# ventiladores.net
KiCad netlist of a schematic drawn in EAGLE
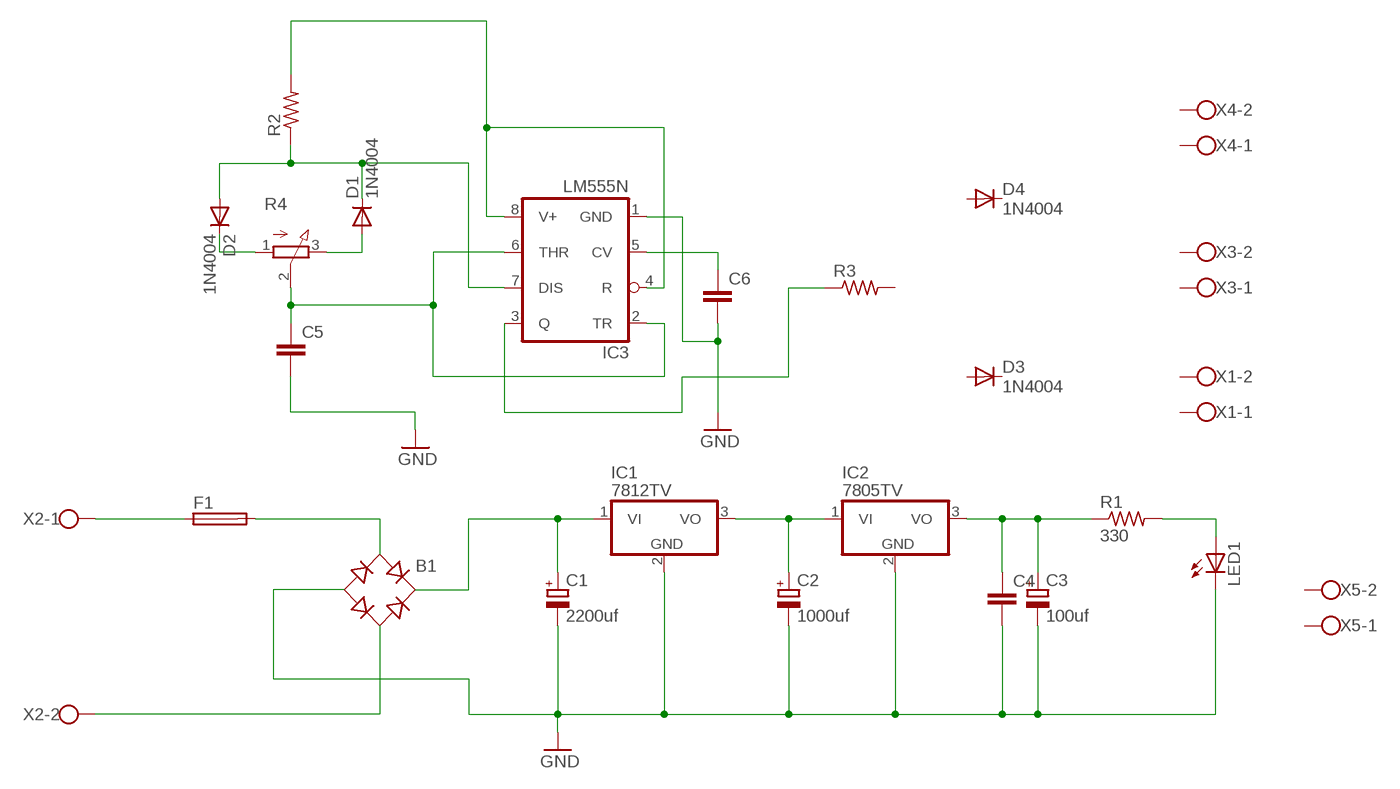
[diagram p0: schematic, sheet 1]

(export (version "E")
  (design (tool "Eeschema 10.0.6"))
  (components
    (comp (ref "B1")
      (value "RB1A")
      (footprint "eagle-import:RB1A")
      (libsource (lib "eagle-import") (part "RB1A"))
    )
    (comp (ref "C1")
      (value "2200uf")
      (footprint "eagle-import:E5-13")
      (libsource (lib "eagle-import") (part "CPOL-EUE5-13"))
    )
    (comp (ref "C2")
      (value "1000uf")
      (footprint "eagle-import:E5-10,5")
      (libsource (lib "eagle-import") (part "CPOL-EUE5-10.5"))
    )
    (comp (ref "C3")
      (value "100uf")
      (footprint "eagle-import:E2,5-6")
      (libsource (lib "eagle-import") (part "CPOL-EUE2.5-6"))
    )
    (comp (ref "C4")
      (value "C2.5/2")
      (footprint "eagle-import:C2.5-2")
      (libsource (lib "eagle-import") (part "C2.5/2"))
    )
    (comp (ref "C5")
      (value "C2.5/2")
      (footprint "eagle-import:C2.5-2")
      (libsource (lib "eagle-import") (part "C2.5/2"))
    )
    (comp (ref "C6")
      (value "C2.5/2")
      (footprint "eagle-import:C2.5-2")
      (libsource (lib "eagle-import") (part "C2.5/2"))
    )
    (comp (ref "D1")
      (value "1N4004")
      (footprint "eagle-import:DO41-10")
      (libsource (lib "eagle-import") (part "1N4004"))
    )
    (comp (ref "D2")
      (value "1N4004")
      (footprint "eagle-import:DO41-10")
      (libsource (lib "eagle-import") (part "1N4004"))
    )
    (comp (ref "D3")
      (value "1N4004")
      (footprint "eagle-import:DO41-10")
      (libsource (lib "eagle-import") (part "1N4004"))
    )
    (comp (ref "D4")
      (value "1N4004")
      (footprint "eagle-import:DO41-10")
      (libsource (lib "eagle-import") (part "1N4004"))
    )
    (comp (ref "F1")
      (value "GSH15")
      (footprint "eagle-import:GSH15")
      (fields (field (name "MPN") "64900001039"))
      (libsource (lib "eagle-import") (part "GSH15"))
    )
    (comp (ref "IC1")
      (value "7812TV")
      (footprint "eagle-import:TO220V")
      (libsource (lib "eagle-import") (part "78TV12"))
    )
    (comp (ref "IC2")
      (value "7805TV")
      (footprint "eagle-import:TO220V")
      (libsource (lib "eagle-import") (part "78TV05"))
    )
    (comp (ref "IC3")
      (value "LM555N")
      (footprint "eagle-import:DIL08")
      (libsource (lib "eagle-import") (part "555NLM"))
    )
    (comp (ref "LED1")
      (value "LED5MM")
      (footprint "eagle-import:LED5MM")
      (libsource (lib "eagle-import") (part "LED5MM"))
    )
    (comp (ref "R1")
      (value "330")
      (footprint "eagle-import:0204_5")
      (libsource (lib "eagle-import") (part "R-US_0204/5"))
    )
    (comp (ref "R2")
      (value "R-US_0207/7")
      (footprint "eagle-import:0207_7")
      (libsource (lib "eagle-import") (part "resistor_R-US_0207/7"))
    )
    (comp (ref "R3")
      (value "R-US_0207/7")
      (footprint "eagle-import:0207_7")
      (libsource (lib "eagle-import") (part "resistor_R-US_0207/7"))
    )
    (comp (ref "R4")
      (value "3RP/1610N")
      (footprint "eagle-import:3RP_1610N")
      (libsource (lib "eagle-import") (part "3RP/1610N"))
    )
    (comp (ref "X1")
      (value "W237-102")
      (footprint "eagle-import:W237-102")
      (fields
        (field (name "MPN") "237-102")
        (field (name "MPN_1") "237-102")
        (field (name "OC_FARNELL") "unknown")
        (field (name "OC_NEWARK") "70K9898")
      )
      (libsource (lib "eagle-import") (part "W237-102"))
    )
    (comp (ref "X2")
      (value "W237-102")
      (footprint "eagle-import:W237-102")
      (fields (field (name "MPN") "237-102"))
      (libsource (lib "eagle-import") (part "W237-102"))
    )
    (comp (ref "X3")
      (value "W237-102")
      (footprint "eagle-import:W237-102")
      (fields
        (field (name "MPN") "237-102")
        (field (name "MPN_1") "237-102")
        (field (name "OC_FARNELL") "unknown")
        (field (name "OC_NEWARK") "70K9898")
      )
      (libsource (lib "eagle-import") (part "W237-102"))
    )
    (comp (ref "X4")
      (value "W237-102")
      (footprint "eagle-import:W237-102")
      (fields
        (field (name "MPN") "237-102")
        (field (name "MPN_1") "237-102")
        (field (name "OC_FARNELL") "unknown")
        (field (name "OC_NEWARK") "70K9898")
      )
      (libsource (lib "eagle-import") (part "W237-102"))
    )
    (comp (ref "X5")
      (value "W237-102")
      (footprint "eagle-import:W237-102")
      (fields
        (field (name "MPN") "237-102")
        (field (name "MPN_1") "237-102")
        (field (name "OC_FARNELL") "unknown")
        (field (name "OC_NEWARK") "70K9898")
      )
      (libsource (lib "eagle-import") (part "W237-102"))
    )
  )
  (nets
    (net (code "1") (name "GND") (class "Default")
      (node (ref "B1") (pin "-") (pinfunction "-_-") (pintype "passive"))
      (node (ref "C1") (pin "-") (pinfunction "-_-") (pintype "passive"))
      (node (ref "C2") (pin "-") (pinfunction "-_-") (pintype "passive"))
      (node (ref "C3") (pin "-") (pinfunction "-_-") (pintype "passive"))
      (node (ref "C4") (pin "2") (pinfunction "2_2") (pintype "passive"))
      (node (ref "C5") (pin "2") (pinfunction "2_2") (pintype "passive"))
      (node (ref "C6") (pin "2") (pinfunction "2_2") (pintype "passive"))
      (node (ref "IC1") (pin "2") (pinfunction "GND_2") (pintype "passive"))
      (node (ref "IC2") (pin "2") (pinfunction "GND_2") (pintype "passive"))
      (node (ref "IC3") (pin "1") (pinfunction "GND_1") (pintype "power_in"))
      (node (ref "LED1") (pin "K") (pinfunction "C_K") (pintype "passive"))
    )
    (net (code "2") (name "Net-(B1-PadAC1)") (class "Default")
      (node (ref "B1") (pin "AC1") (pinfunction "AC1_AC1") (pintype "passive"))
      (node (ref "F1") (pin "2") (pinfunction "2_2") (pintype "passive"))
    )
    (net (code "3") (name "Net-(IC1-VI)") (class "Default")
      (node (ref "B1") (pin "+") (pinfunction "+_+") (pintype "passive"))
      (node (ref "C1") (pin "+") (pinfunction "+_+") (pintype "passive"))
      (node (ref "IC1") (pin "1") (pinfunction "VI_1") (pintype "input"))
    )
    (net (code "4") (name "Net-(IC1-VO)") (class "Default")
      (node (ref "C2") (pin "+") (pinfunction "+_+") (pintype "passive"))
      (node (ref "IC1") (pin "3") (pinfunction "VO_3") (pintype "passive"))
      (node (ref "IC2") (pin "1") (pinfunction "VI_1") (pintype "input"))
    )
    (net (code "5") (name "Net-(IC2-VO)") (class "Default")
      (node (ref "C3") (pin "+") (pinfunction "+_+") (pintype "passive"))
      (node (ref "C4") (pin "1") (pinfunction "1_1") (pintype "passive"))
      (node (ref "IC2") (pin "3") (pinfunction "VO_3") (pintype "passive"))
      (node (ref "R1") (pin "1") (pinfunction "1_1") (pintype "passive"))
    )
    (net (code "6") (name "Net-(IC3-CV)") (class "Default")
      (node (ref "C6") (pin "1") (pinfunction "1_1") (pintype "passive"))
      (node (ref "IC3") (pin "5") (pinfunction "CV_5") (pintype "input"))
    )
    (net (code "7") (name "Net-(IC3-DIS)") (class "Default")
      (node (ref "D1") (pin "C") (pinfunction "C_C") (pintype "passive"))
      (node (ref "D2") (pin "A") (pinfunction "A_A") (pintype "passive"))
      (node (ref "IC3") (pin "7") (pinfunction "DIS_7") (pintype "input"))
      (node (ref "R2") (pin "1") (pinfunction "1_1") (pintype "passive"))
    )
    (net (code "8") (name "Net-(IC3-Q)") (class "Default")
      (node (ref "IC3") (pin "3") (pinfunction "Q_3") (pintype "output"))
      (node (ref "R3") (pin "1") (pinfunction "1_1") (pintype "passive"))
    )
    (net (code "9") (name "Net-(IC3-R)") (class "Default")
      (node (ref "IC3") (pin "4") (pinfunction "R_4") (pintype "input"))
      (node (ref "IC3") (pin "8") (pinfunction "V+_8") (pintype "power_in"))
      (node (ref "R2") (pin "2") (pinfunction "2_2") (pintype "passive"))
    )
    (net (code "10") (name "Net-(IC3-THR)") (class "Default")
      (node (ref "C5") (pin "1") (pinfunction "1_1") (pintype "passive"))
      (node (ref "IC3") (pin "2") (pinfunction "TR_2") (pintype "input"))
      (node (ref "IC3") (pin "6") (pinfunction "THR_6") (pintype "input"))
      (node (ref "R4") (pin "2") (pinfunction "S_2") (pintype "passive"))
    )
    (net (code "11") (name "Net-(LED1-PadA)") (class "Default")
      (node (ref "LED1") (pin "A") (pinfunction "A_A") (pintype "passive"))
      (node (ref "R1") (pin "2") (pinfunction "2_2") (pintype "passive"))
    )
    (net (code "12") (name "Net-(R4-A)") (class "Default")
      (node (ref "D2") (pin "C") (pinfunction "C_C") (pintype "passive"))
      (node (ref "R4") (pin "1") (pinfunction "A_1") (pintype "passive"))
    )
    (net (code "13") (name "Net-(R4-E)") (class "Default")
      (node (ref "D1") (pin "A") (pinfunction "A_A") (pintype "passive"))
      (node (ref "R4") (pin "3") (pinfunction "E_3") (pintype "passive"))
    )
    (net (code "14") (name "Net-(X2A-KL)") (class "Default")
      (node (ref "F1") (pin "1") (pinfunction "1_1") (pintype "passive"))
      (node (ref "X2") (pin "1") (pinfunction "KL_1") (pintype "passive"))
    )
    (net (code "15") (name "Net-(X2B-KL)") (class "Default")
      (node (ref "B1") (pin "AC2") (pinfunction "AC2_AC2") (pintype "passive"))
      (node (ref "X2") (pin "2") (pinfunction "KL_2") (pintype "passive"))
    )
    (net (code "16") (name "unconnected-(D3-PadA)") (class "Default")
      (node (ref "D3") (pin "A") (pinfunction "A_A") (pintype "passive"))
    )
    (net (code "17") (name "unconnected-(D3-PadC)") (class "Default")
      (node (ref "D3") (pin "C") (pinfunction "C_C") (pintype "passive"))
    )
    (net (code "18") (name "unconnected-(D4-PadA)") (class "Default")
      (node (ref "D4") (pin "A") (pinfunction "A_A") (pintype "passive"))
    )
    (net (code "19") (name "unconnected-(D4-PadC)") (class "Default")
      (node (ref "D4") (pin "C") (pinfunction "C_C") (pintype "passive"))
    )
    (net (code "20") (name "unconnected-(R3-Pad2)") (class "Default")
      (node (ref "R3") (pin "2") (pinfunction "2_2") (pintype "passive"))
    )
    (net (code "21") (name "unconnected-(X1A-KL-Pad1)") (class "Default")
      (node (ref "X1") (pin "1") (pinfunction "KL_1") (pintype "passive"))
    )
    (net (code "22") (name "unconnected-(X1B-KL-Pad2)") (class "Default")
      (node (ref "X1") (pin "2") (pinfunction "KL_2") (pintype "passive"))
    )
    (net (code "23") (name "unconnected-(X3A-KL-Pad1)") (class "Default")
      (node (ref "X3") (pin "1") (pinfunction "KL_1") (pintype "passive"))
    )
    (net (code "24") (name "unconnected-(X3B-KL-Pad2)") (class "Default")
      (node (ref "X3") (pin "2") (pinfunction "KL_2") (pintype "passive"))
    )
    (net (code "25") (name "unconnected-(X4A-KL-Pad1)") (class "Default")
      (node (ref "X4") (pin "1") (pinfunction "KL_1") (pintype "passive"))
    )
    (net (code "26") (name "unconnected-(X4B-KL-Pad2)") (class "Default")
      (node (ref "X4") (pin "2") (pinfunction "KL_2") (pintype "passive"))
    )
    (net (code "27") (name "unconnected-(X5A-KL-Pad1)") (class "Default")
      (node (ref "X5") (pin "1") (pinfunction "KL_1") (pintype "passive"))
    )
    (net (code "28") (name "unconnected-(X5B-KL-Pad2)") (class "Default")
      (node (ref "X5") (pin "2") (pinfunction "KL_2") (pintype "passive"))
    )
  )
)
